# SSL-Motherboard.net
KiCad netlist of a schematic drawn in Altium Designer
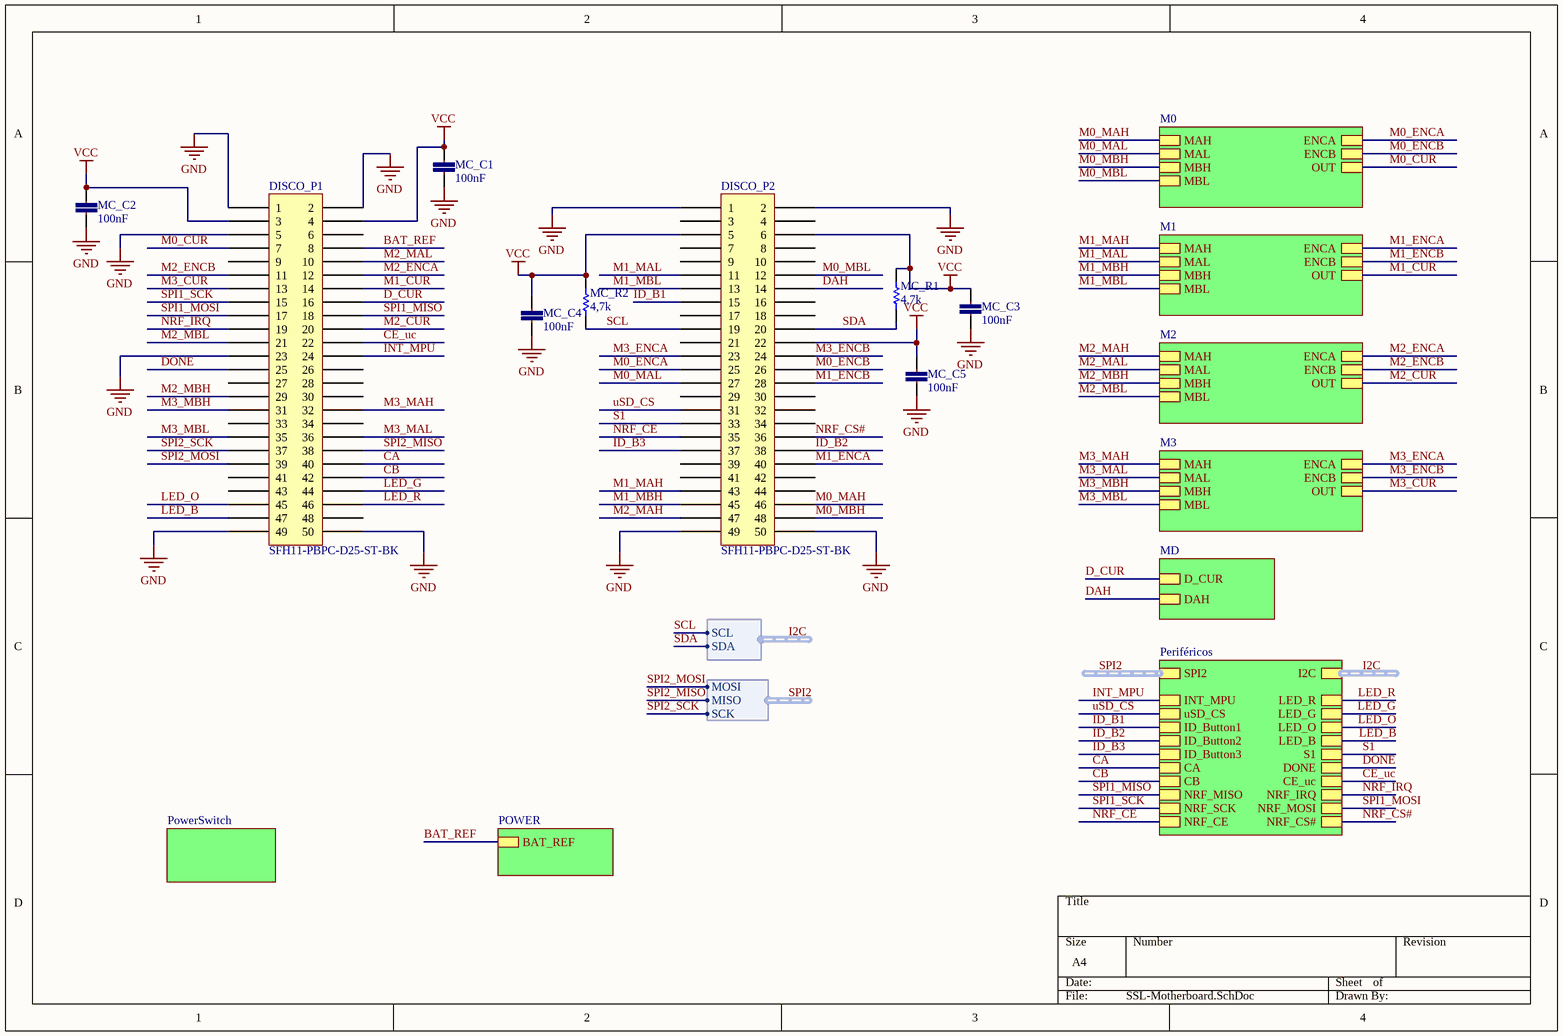
[diagram p0: SSL-Motherboard.SchDoc]

(export (version "E")
  (design (tool "Eeschema 10.0.6"))
  (components
    (comp (ref "DISCO_P1")
      (value "SFH11-PBPC-D25-ST-BK")
      (footprint "25x02_Conector_Female")
      (description "50 Position Header Connector 0.100\" (2.54mm) Through Hole Gold")
      (libsource (lib "Schlib1") (part "25x02_Conector_Female"))
    )
    (comp (ref "DISCO_P2")
      (value "SFH11-PBPC-D25-ST-BK")
      (footprint "25x02_Conector_Female")
      (description "50 Position Header Connector 0.100\" (2.54mm) Through Hole Gold")
      (libsource (lib "Schlib1") (part "25x02_Conector_Female"))
    )
    (comp (ref "MC_C1")
      (value "100nF")
      (footprint "0402-CAP")
      (description "CAP CER 0.1UF 10V 20% X5R 0402")
      (fields (field (name "PART NO") "VJ0402V104ZXQPBC"))
      (libsource (lib "IMBEL") (part "CC0402-100nF-A.12"))
    )
    (comp (ref "MC_C2")
      (value "100nF")
      (footprint "0402-CAP")
      (description "CAP CER 0.1UF 10V 20% X5R 0402")
      (fields (field (name "PART NO") "VJ0402V104ZXQPBC"))
      (libsource (lib "") (part "CC0402-100nF-A.12_1"))
    )
    (comp (ref "MC_C3")
      (value "100nF")
      (footprint "0402-CAP")
      (description "CAP CER 0.1UF 10V 20% X5R 0402")
      (fields (field (name "PART NO") "VJ0402V104ZXQPBC"))
      (libsource (lib "IMBEL") (part "CC0402-100nF-A.12"))
    )
    (comp (ref "MC_C4")
      (value "100nF")
      (footprint "0402-CAP")
      (description "CAP CER 0.1UF 10V 20% X5R 0402")
      (fields (field (name "PART NO") "VJ0402V104ZXQPBC"))
      (libsource (lib "IMBEL") (part "CC0402-100nF-A.12"))
    )
    (comp (ref "MC_C5")
      (value "100nF")
      (footprint "0402-CAP")
      (description "CAP CER 0.1UF 10V 20% X5R 0402")
      (fields (field (name "PART NO") "VJ0402V104ZXQPBC"))
      (libsource (lib "IMBEL") (part "CC0402-100nF-A.12"))
    )
    (comp (ref "MC_R1")
      (value "4,7k")
      (footprint "0402")
      (description "Resistor")
      (fields (field (name "PUBLISHER") "Altium Limited"))
      (libsource (lib "Miscellaneous Devices") (part "Res1"))
    )
    (comp (ref "MC_R2")
      (value "4,7k")
      (footprint "0402")
      (description "Resistor")
      (fields (field (name "PUBLISHER") "Altium Limited"))
      (libsource (lib "Miscellaneous Devices") (part "Res1"))
    )
  )
  (nets
    (net (code "5") (name "/BAT_REF") (class "Default")
      (node (ref "DISCO_P1") (pin "8") (pinfunction "8_8") (pintype "passive"))
    )
    (net (code "6") (name "/CA") (class "Default")
      (node (ref "DISCO_P1") (pin "40") (pinfunction "40_40") (pintype "passive"))
    )
    (net (code "7") (name "/CB") (class "Default")
      (node (ref "DISCO_P1") (pin "42") (pinfunction "42_42") (pintype "passive"))
    )
    (net (code "8") (name "/CE_uc") (class "Default")
      (node (ref "DISCO_P1") (pin "22") (pinfunction "22_22") (pintype "passive"))
    )
    (net (code "9") (name "/DAH") (class "Default")
      (node (ref "DISCO_P2") (pin "14") (pinfunction "14_14") (pintype "passive"))
    )
    (net (code "10") (name "/DONE") (class "Default")
      (node (ref "DISCO_P1") (pin "25") (pinfunction "25_25") (pintype "passive"))
    )
    (net (code "11") (name "/D_CUR") (class "Default")
      (node (ref "DISCO_P1") (pin "16") (pinfunction "16_16") (pintype "passive"))
    )
    (net (code "13") (name "/ID_B1") (class "Default")
      (node (ref "DISCO_P2") (pin "15") (pinfunction "15_15") (pintype "passive"))
    )
    (net (code "14") (name "/ID_B2") (class "Default")
      (node (ref "DISCO_P2") (pin "38") (pinfunction "38_38") (pintype "passive"))
    )
    (net (code "15") (name "/ID_B3") (class "Default")
      (node (ref "DISCO_P2") (pin "37") (pinfunction "37_37") (pintype "passive"))
    )
    (net (code "16") (name "/INT_MPU") (class "Default")
      (node (ref "DISCO_P1") (pin "24") (pinfunction "24_24") (pintype "passive"))
    )
    (net (code "17") (name "/LED_B") (class "Default")
      (node (ref "DISCO_P1") (pin "47") (pinfunction "47_47") (pintype "passive"))
    )
    (net (code "18") (name "/LED_G") (class "Default")
      (node (ref "DISCO_P1") (pin "44") (pinfunction "44_44") (pintype "passive"))
    )
    (net (code "19") (name "/LED_O") (class "Default")
      (node (ref "DISCO_P1") (pin "45") (pinfunction "45_45") (pintype "passive"))
    )
    (net (code "20") (name "/LED_R") (class "Default")
      (node (ref "DISCO_P1") (pin "46") (pinfunction "46_46") (pintype "passive"))
    )
    (net (code "21") (name "/M0_CUR") (class "Default")
      (node (ref "DISCO_P1") (pin "7") (pinfunction "7_7") (pintype "passive"))
    )
    (net (code "22") (name "/M0_ENCA") (class "Default")
      (node (ref "DISCO_P2") (pin "25") (pinfunction "25_25") (pintype "passive"))
    )
    (net (code "23") (name "/M0_ENCB") (class "Default")
      (node (ref "DISCO_P2") (pin "26") (pinfunction "26_26") (pintype "passive"))
    )
    (net (code "24") (name "/M0_MAH") (class "Default")
      (node (ref "DISCO_P2") (pin "46") (pinfunction "46_46") (pintype "passive"))
    )
    (net (code "25") (name "/M0_MAL") (class "Default")
      (node (ref "DISCO_P2") (pin "27") (pinfunction "27_27") (pintype "passive"))
    )
    (net (code "26") (name "/M0_MBH") (class "Default")
      (node (ref "DISCO_P2") (pin "48") (pinfunction "48_48") (pintype "passive"))
    )
    (net (code "27") (name "/M0_MBL") (class "Default")
      (node (ref "DISCO_P2") (pin "12") (pinfunction "12_12") (pintype "passive"))
    )
    (net (code "28") (name "/M1_CUR") (class "Default")
      (node (ref "DISCO_P1") (pin "14") (pinfunction "14_14") (pintype "passive"))
    )
    (net (code "29") (name "/M1_ENCA") (class "Default")
      (node (ref "DISCO_P2") (pin "40") (pinfunction "40_40") (pintype "passive"))
    )
    (net (code "30") (name "/M1_ENCB") (class "Default")
      (node (ref "DISCO_P2") (pin "28") (pinfunction "28_28") (pintype "passive"))
    )
    (net (code "31") (name "/M1_MAH") (class "Default")
      (node (ref "DISCO_P2") (pin "43") (pinfunction "43_43") (pintype "passive"))
    )
    (net (code "32") (name "/M1_MAL") (class "Default")
      (node (ref "DISCO_P2") (pin "11") (pinfunction "11_11") (pintype "passive"))
    )
    (net (code "33") (name "/M1_MBH") (class "Default")
      (node (ref "DISCO_P2") (pin "45") (pinfunction "45_45") (pintype "passive"))
    )
    (net (code "34") (name "/M1_MBL") (class "Default")
      (node (ref "DISCO_P2") (pin "13") (pinfunction "13_13") (pintype "passive"))
    )
    (net (code "35") (name "/M2_CUR") (class "Default")
      (node (ref "DISCO_P1") (pin "20") (pinfunction "20_20") (pintype "passive"))
    )
    (net (code "36") (name "/M2_ENCA") (class "Default")
      (node (ref "DISCO_P1") (pin "12") (pinfunction "12_12") (pintype "passive"))
    )
    (net (code "37") (name "/M2_ENCB") (class "Default")
      (node (ref "DISCO_P1") (pin "11") (pinfunction "11_11") (pintype "passive"))
    )
    (net (code "38") (name "/M2_MAH") (class "Default")
      (node (ref "DISCO_P2") (pin "47") (pinfunction "47_47") (pintype "passive"))
    )
    (net (code "39") (name "/M2_MAL") (class "Default")
      (node (ref "DISCO_P1") (pin "10") (pinfunction "10_10") (pintype "passive"))
    )
    (net (code "40") (name "/M2_MBH") (class "Default")
      (node (ref "DISCO_P1") (pin "29") (pinfunction "29_29") (pintype "passive"))
    )
    (net (code "41") (name "/M2_MBL") (class "Default")
      (node (ref "DISCO_P1") (pin "21") (pinfunction "21_21") (pintype "passive"))
    )
    (net (code "42") (name "/M3_CUR") (class "Default")
      (node (ref "DISCO_P1") (pin "13") (pinfunction "13_13") (pintype "passive"))
    )
    (net (code "43") (name "/M3_ENCA") (class "Default")
      (node (ref "DISCO_P2") (pin "23") (pinfunction "23_23") (pintype "passive"))
    )
    (net (code "44") (name "/M3_ENCB") (class "Default")
      (node (ref "DISCO_P2") (pin "24") (pinfunction "24_24") (pintype "passive"))
    )
    (net (code "45") (name "/M3_MAH") (class "Default")
      (node (ref "DISCO_P1") (pin "32") (pinfunction "32_32") (pintype "passive"))
    )
    (net (code "46") (name "/M3_MAL") (class "Default")
      (node (ref "DISCO_P1") (pin "36") (pinfunction "36_36") (pintype "passive"))
    )
    (net (code "47") (name "/M3_MBH") (class "Default")
      (node (ref "DISCO_P1") (pin "31") (pinfunction "31_31") (pintype "passive"))
    )
    (net (code "48") (name "/M3_MBL") (class "Default")
      (node (ref "DISCO_P1") (pin "35") (pinfunction "35_35") (pintype "passive"))
    )
    (net (code "49") (name "/NRF_CE") (class "Default")
      (node (ref "DISCO_P2") (pin "35") (pinfunction "35_35") (pintype "passive"))
    )
    (net (code "50") (name "/NRF_CS#") (class "Default")
      (node (ref "DISCO_P2") (pin "36") (pinfunction "36_36") (pintype "passive"))
    )
    (net (code "51") (name "/NRF_IRQ") (class "Default")
      (node (ref "DISCO_P1") (pin "19") (pinfunction "19_19") (pintype "passive"))
    )
    (net (code "52") (name "/S1") (class "Default")
      (node (ref "DISCO_P2") (pin "33") (pinfunction "33_33") (pintype "passive"))
    )
    (net (code "53") (name "/SCL") (class "Default")
      (node (ref "DISCO_P2") (pin "19") (pinfunction "19_19") (pintype "passive"))
      (node (ref "MC_R2") (pin "1") (pinfunction "1_1") (pintype "passive"))
    )
    (net (code "54") (name "/SDA") (class "Default")
      (node (ref "DISCO_P2") (pin "20") (pinfunction "20_20") (pintype "passive"))
      (node (ref "MC_R1") (pin "1") (pinfunction "1_1") (pintype "passive"))
    )
    (net (code "55") (name "/SPI1_MISO") (class "Default")
      (node (ref "DISCO_P1") (pin "18") (pinfunction "18_18") (pintype "passive"))
    )
    (net (code "56") (name "/SPI1_MOSI") (class "Default")
      (node (ref "DISCO_P1") (pin "17") (pinfunction "17_17") (pintype "passive"))
    )
    (net (code "57") (name "/SPI1_SCK") (class "Default")
      (node (ref "DISCO_P1") (pin "15") (pinfunction "15_15") (pintype "passive"))
    )
    (net (code "58") (name "/SPI2_MISO") (class "Default")
      (node (ref "DISCO_P1") (pin "38") (pinfunction "38_38") (pintype "passive"))
    )
    (net (code "59") (name "/SPI2_MOSI") (class "Default")
      (node (ref "DISCO_P1") (pin "39") (pinfunction "39_39") (pintype "passive"))
    )
    (net (code "60") (name "/SPI2_SCK") (class "Default")
      (node (ref "DISCO_P1") (pin "37") (pinfunction "37_37") (pintype "passive"))
    )
    (net (code "62") (name "/uSD_CS") (class "Default")
      (node (ref "DISCO_P2") (pin "31") (pinfunction "31_31") (pintype "passive"))
    )
    (net (code "65") (name "GND") (class "Default")
      (node (ref "DISCO_P1") (pin "1") (pinfunction "1_1") (pintype "passive"))
      (node (ref "DISCO_P1") (pin "2") (pinfunction "2_2") (pintype "passive"))
      (node (ref "DISCO_P1") (pin "23") (pinfunction "23_23") (pintype "passive"))
      (node (ref "DISCO_P1") (pin "49") (pinfunction "49_49") (pintype "passive"))
      (node (ref "DISCO_P1") (pin "5") (pinfunction "5_5") (pintype "passive"))
      (node (ref "DISCO_P1") (pin "50") (pinfunction "50_50") (pintype "passive"))
      (node (ref "DISCO_P2") (pin "1") (pinfunction "1_1") (pintype "passive"))
      (node (ref "DISCO_P2") (pin "2") (pinfunction "2_2") (pintype "passive"))
      (node (ref "DISCO_P2") (pin "49") (pinfunction "49_49") (pintype "passive"))
      (node (ref "DISCO_P2") (pin "50") (pinfunction "50_50") (pintype "passive"))
      (node (ref "MC_C1") (pin "1") (pinfunction "1_1") (pintype "passive"))
      (node (ref "MC_C2") (pin "2") (pinfunction "2_2") (pintype "passive"))
      (node (ref "MC_C3") (pin "1") (pinfunction "1_1") (pintype "passive"))
      (node (ref "MC_C4") (pin "1") (pinfunction "1_1") (pintype "passive"))
      (node (ref "MC_C5") (pin "1") (pinfunction "1_1") (pintype "passive"))
    )
    (net (code "66") (name "VCC") (class "Default")
      (node (ref "DISCO_P1") (pin "3") (pinfunction "3_3") (pintype "passive"))
      (node (ref "DISCO_P1") (pin "4") (pinfunction "4_4") (pintype "passive"))
      (node (ref "DISCO_P2") (pin "22") (pinfunction "22_22") (pintype "passive"))
      (node (ref "DISCO_P2") (pin "5") (pinfunction "5_5") (pintype "passive"))
      (node (ref "DISCO_P2") (pin "6") (pinfunction "6_6") (pintype "passive"))
      (node (ref "MC_C1") (pin "2") (pinfunction "2_2") (pintype "passive"))
      (node (ref "MC_C2") (pin "1") (pinfunction "1_1") (pintype "passive"))
      (node (ref "MC_C3") (pin "2") (pinfunction "2_2") (pintype "passive"))
      (node (ref "MC_C4") (pin "2") (pinfunction "2_2") (pintype "passive"))
      (node (ref "MC_C5") (pin "2") (pinfunction "2_2") (pintype "passive"))
      (node (ref "MC_R1") (pin "2") (pinfunction "2_2") (pintype "passive"))
      (node (ref "MC_R2") (pin "2") (pinfunction "2_2") (pintype "passive"))
    )
    (net (code "67") (name "unconnected-(DISCO_P1-Pad6)") (class "Default")
      (node (ref "DISCO_P1") (pin "6") (pinfunction "6_6") (pintype "passive"))
    )
    (net (code "68") (name "unconnected-(DISCO_P1-Pad9)") (class "Default")
      (node (ref "DISCO_P1") (pin "9") (pinfunction "9_9") (pintype "passive"))
    )
    (net (code "69") (name "unconnected-(DISCO_P1-Pad26)") (class "Default")
      (node (ref "DISCO_P1") (pin "26") (pinfunction "26_26") (pintype "passive"))
    )
    (net (code "70") (name "unconnected-(DISCO_P1-Pad27)") (class "Default")
      (node (ref "DISCO_P1") (pin "27") (pinfunction "27_27") (pintype "passive"))
    )
    (net (code "71") (name "unconnected-(DISCO_P1-Pad28)") (class "Default")
      (node (ref "DISCO_P1") (pin "28") (pinfunction "28_28") (pintype "passive"))
    )
    (net (code "72") (name "unconnected-(DISCO_P1-Pad30)") (class "Default")
      (node (ref "DISCO_P1") (pin "30") (pinfunction "30_30") (pintype "passive"))
    )
    (net (code "73") (name "unconnected-(DISCO_P1-Pad33)") (class "Default")
      (node (ref "DISCO_P1") (pin "33") (pinfunction "33_33") (pintype "passive"))
    )
    (net (code "74") (name "unconnected-(DISCO_P1-Pad34)") (class "Default")
      (node (ref "DISCO_P1") (pin "34") (pinfunction "34_34") (pintype "passive"))
    )
    (net (code "75") (name "unconnected-(DISCO_P1-Pad41)") (class "Default")
      (node (ref "DISCO_P1") (pin "41") (pinfunction "41_41") (pintype "passive"))
    )
    (net (code "76") (name "unconnected-(DISCO_P1-Pad43)") (class "Default")
      (node (ref "DISCO_P1") (pin "43") (pinfunction "43_43") (pintype "passive"))
    )
    (net (code "77") (name "unconnected-(DISCO_P1-Pad48)") (class "Default")
      (node (ref "DISCO_P1") (pin "48") (pinfunction "48_48") (pintype "passive"))
    )
    (net (code "78") (name "unconnected-(DISCO_P2-Pad3)") (class "Default")
      (node (ref "DISCO_P2") (pin "3") (pinfunction "3_3") (pintype "passive"))
    )
    (net (code "79") (name "unconnected-(DISCO_P2-Pad4)") (class "Default")
      (node (ref "DISCO_P2") (pin "4") (pinfunction "4_4") (pintype "passive"))
    )
    (net (code "80") (name "unconnected-(DISCO_P2-Pad7)") (class "Default")
      (node (ref "DISCO_P2") (pin "7") (pinfunction "7_7") (pintype "passive"))
    )
    (net (code "81") (name "unconnected-(DISCO_P2-Pad8)") (class "Default")
      (node (ref "DISCO_P2") (pin "8") (pinfunction "8_8") (pintype "passive"))
    )
    (net (code "82") (name "unconnected-(DISCO_P2-Pad9)") (class "Default")
      (node (ref "DISCO_P2") (pin "9") (pinfunction "9_9") (pintype "passive"))
    )
    (net (code "83") (name "unconnected-(DISCO_P2-Pad10)") (class "Default")
      (node (ref "DISCO_P2") (pin "10") (pinfunction "10_10") (pintype "passive"))
    )
    (net (code "84") (name "unconnected-(DISCO_P2-Pad16)") (class "Default")
      (node (ref "DISCO_P2") (pin "16") (pinfunction "16_16") (pintype "passive"))
    )
    (net (code "85") (name "unconnected-(DISCO_P2-Pad17)") (class "Default")
      (node (ref "DISCO_P2") (pin "17") (pinfunction "17_17") (pintype "passive"))
    )
    (net (code "86") (name "unconnected-(DISCO_P2-Pad18)") (class "Default")
      (node (ref "DISCO_P2") (pin "18") (pinfunction "18_18") (pintype "passive"))
    )
    (net (code "87") (name "unconnected-(DISCO_P2-Pad21)") (class "Default")
      (node (ref "DISCO_P2") (pin "21") (pinfunction "21_21") (pintype "passive"))
    )
    (net (code "88") (name "unconnected-(DISCO_P2-Pad29)") (class "Default")
      (node (ref "DISCO_P2") (pin "29") (pinfunction "29_29") (pintype "passive"))
    )
    (net (code "89") (name "unconnected-(DISCO_P2-Pad30)") (class "Default")
      (node (ref "DISCO_P2") (pin "30") (pinfunction "30_30") (pintype "passive"))
    )
    (net (code "90") (name "unconnected-(DISCO_P2-Pad32)") (class "Default")
      (node (ref "DISCO_P2") (pin "32") (pinfunction "32_32") (pintype "passive"))
    )
    (net (code "91") (name "unconnected-(DISCO_P2-Pad34)") (class "Default")
      (node (ref "DISCO_P2") (pin "34") (pinfunction "34_34") (pintype "passive"))
    )
    (net (code "92") (name "unconnected-(DISCO_P2-Pad39)") (class "Default")
      (node (ref "DISCO_P2") (pin "39") (pinfunction "39_39") (pintype "passive"))
    )
    (net (code "93") (name "unconnected-(DISCO_P2-Pad41)") (class "Default")
      (node (ref "DISCO_P2") (pin "41") (pinfunction "41_41") (pintype "passive"))
    )
    (net (code "94") (name "unconnected-(DISCO_P2-Pad42)") (class "Default")
      (node (ref "DISCO_P2") (pin "42") (pinfunction "42_42") (pintype "passive"))
    )
    (net (code "95") (name "unconnected-(DISCO_P2-Pad44)") (class "Default")
      (node (ref "DISCO_P2") (pin "44") (pinfunction "44_44") (pintype "passive"))
    )
  )
)
